# KeypadDisplayConnectors.net
KiCad netlist of a schematic drawn in Altium Designer
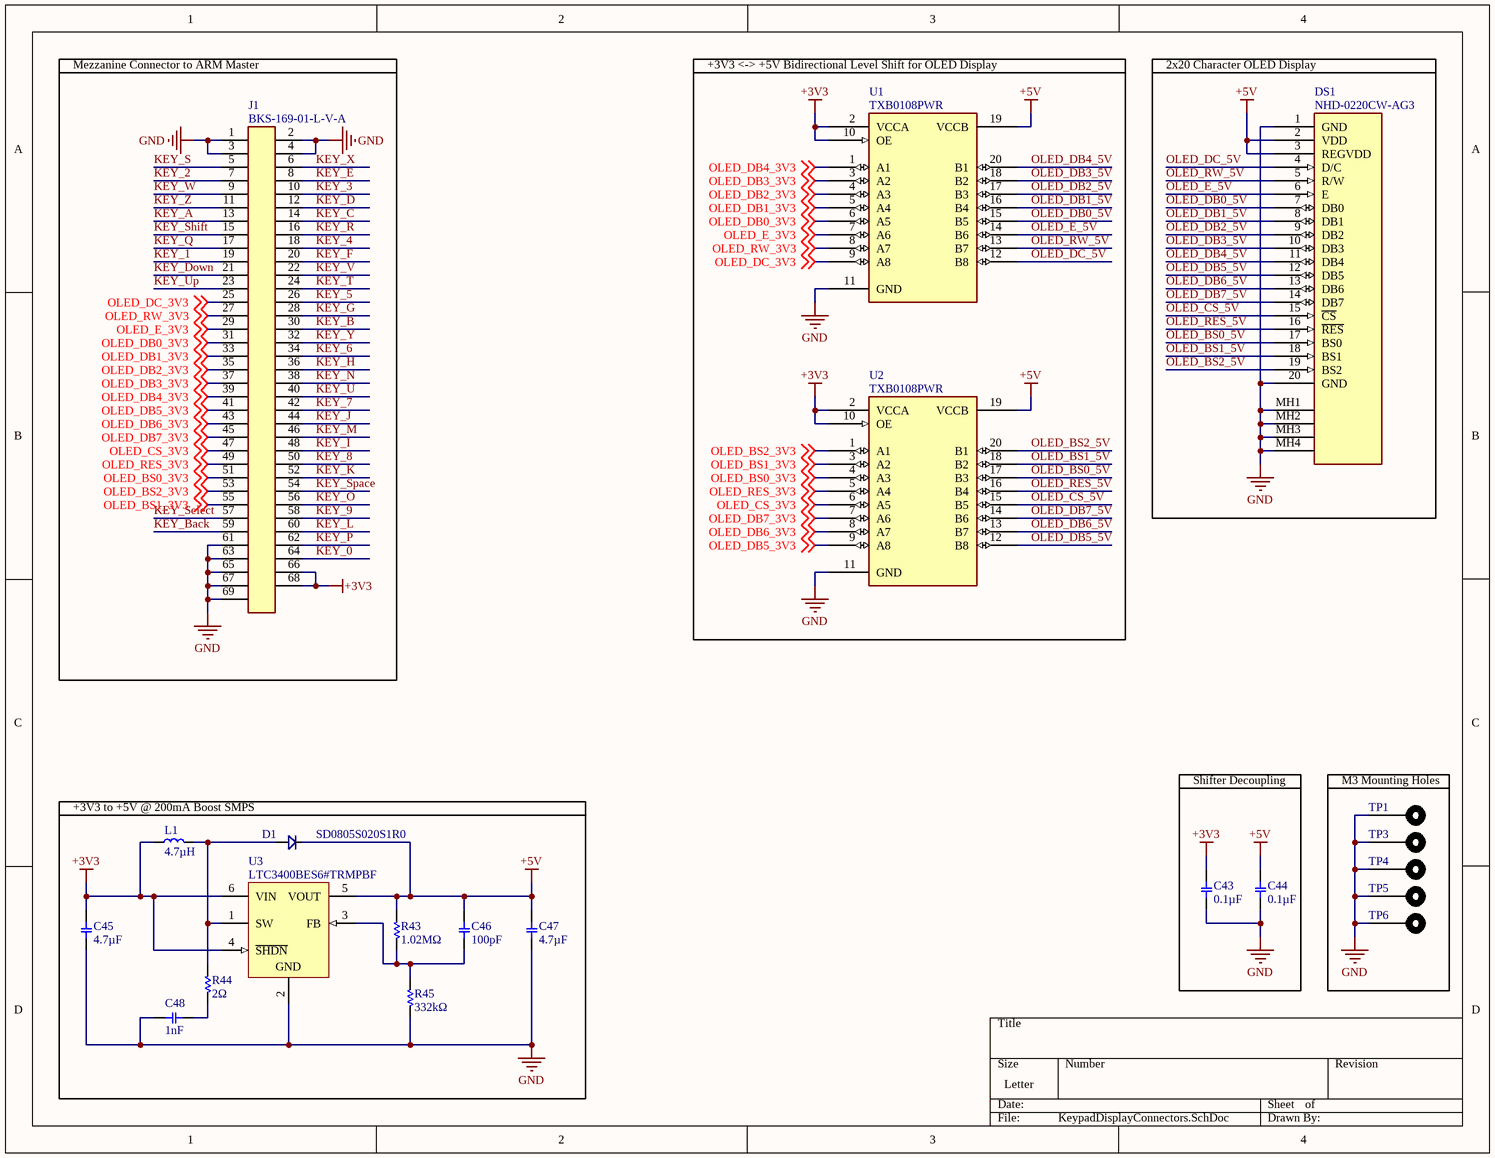
[diagram p0: KeypadDisplayConnectors.SchDoc]

(export (version "E")
  (design (tool "Eeschema 10.0.6"))
  (components
    (comp (ref "C43")
      (value "0.1µF")
      (footprint "C0805(2012)_NP_med")
      (description "SMT Capacitor")
      (fields (field (name "TOLERANCE") "X7R"))
      (libsource (lib "ChipComponents") (part "CPN_SMT"))
    )
    (comp (ref "C44")
      (value "0.1µF")
      (footprint "C0805(2012)_NP_med")
      (description "SMT Capacitor")
      (fields (field (name "TOLERANCE") "X7R"))
      (libsource (lib "ChipComponents") (part "CPN_SMT"))
    )
    (comp (ref "C45")
      (value "4.7µF")
      (footprint "C0805(2012)_NP_med")
      (description "SMT Capacitor")
      (fields (field (name "MANUFACTURER") "Taiyo Yuden") (field (name "PART NUMBER") "JMK212BJ475MG"))
      (libsource (lib "ChipComponents") (part "CPN_SMT"))
    )
    (comp (ref "C46")
      (value "100pF")
      (footprint "C0805(2012)_NP_med")
      (description "SMT Capacitor")
      (fields (field (name "TOLERANCE") "X7R"))
      (libsource (lib "ChipComponents") (part "CPN_SMT"))
    )
    (comp (ref "C47")
      (value "4.7µF")
      (footprint "C0805(2012)_NP_med")
      (description "SMT Capacitor")
      (fields (field (name "MANUFACTURER") "Taiyo Yuden") (field (name "PART NUMBER") "JMK212BJ475MG"))
      (libsource (lib "ChipComponents") (part "CPN_SMT"))
    )
    (comp (ref "C48")
      (value "1nF")
      (footprint "C0805(2012)_NP_med")
      (description "SMT Capacitor")
      (fields (field (name "TOLERANCE") "X7R"))
      (libsource (lib "ChipComponents") (part "CPN_SMT"))
    )
    (comp (ref "D1")
      (value "SD0805S020S1R0")
      (footprint "C0805(2012)_P_med")
      (description "SMT LED")
      (fields (field (name "MANUFACTURER") "AVX"))
      (libsource (lib "ChipComponents") (part "DIODE_sMT"))
    )
    (comp (ref "DS1")
      (value "NHD-0220CW-AG3")
      (footprint "Newhaven NHD-0220CW-AG3")
      (fields (field (name "MANUFACTURER") "Newhaven Display Intl"))
      (libsource (lib "RFIDSchematicLibrary") (part "NewHaven NHD-0220CW-AG3"))
    )
    (comp (ref "J1")
      (value "BKS-169-01-L-V-A")
      (footprint "SAMTEC BKS-169-01-L-V-A")
      (description "CONN HDR 69POS 1MM SMD GLD")
      (libsource (lib "RFIDSchematicLibrary") (part "Samtec BKS-169-01-L-V-A"))
    )
    (comp (ref "L1")
      (value "4.7µH")
      (footprint "C0805(2012)_NP_med")
      (description "SMT Inductor")
      (fields (field (name "MANUFACTURER") "Murata") (field (name "PART NUMBER") "LQM2MPN4R7MG0L"))
      (libsource (lib "ChipComponents") (part "IND_SMT"))
    )
    (comp (ref "R43")
      (value "1.02MΩ")
      (footprint "R0805(2012)_med")
      (description "SMT resistor")
      (fields (field (name "TOLERANCE") "1%"))
      (libsource (lib "ChipComponents") (part "RES_SMT"))
    )
    (comp (ref "R44")
      (value "2Ω")
      (footprint "R0805(2012)_med")
      (description "SMT resistor")
      (fields (field (name "TOLERANCE") "1%"))
      (libsource (lib "ChipComponents") (part "RES_SMT"))
    )
    (comp (ref "R45")
      (value "332kΩ")
      (footprint "R0805(2012)_med")
      (description "SMT resistor")
      (fields (field (name "TOLERANCE") "1%"))
      (libsource (lib "ChipComponents") (part "RES_SMT"))
    )
    (comp (ref "TP1")
      (value "Testpoint")
      (footprint "M3x0.5 Hole")
      (libsource (lib "RFIDSchematicLibrary") (part "Testpoint"))
    )
    (comp (ref "TP3")
      (value "Testpoint")
      (footprint "M3x0.5 Hole")
      (libsource (lib "RFIDSchematicLibrary") (part "Testpoint"))
    )
    (comp (ref "TP4")
      (value "Testpoint")
      (footprint "M3x0.5 Hole")
      (libsource (lib "RFIDSchematicLibrary") (part "Testpoint"))
    )
    (comp (ref "TP5")
      (value "Testpoint")
      (footprint "M3x0.5 Hole")
      (libsource (lib "RFIDSchematicLibrary") (part "Testpoint"))
    )
    (comp (ref "TP6")
      (value "Testpoint")
      (footprint "M3x0.5 Hole")
      (libsource (lib "RFIDSchematicLibrary") (part "Testpoint"))
    )
    (comp (ref "U1")
      (value "TXB0108PWR")
      (footprint "TI 20 Pin PW (R-PDSO-G20)")
      (description "IC 8-BIT TRNSTR 15KV ESD 20TSSOP")
      (fields (field (name "MANUFACTURER") "Texas Instruments"))
      (libsource (lib "RFIDSchematicLibrary") (part "TI TXB0108PWR"))
    )
    (comp (ref "U2")
      (value "TXB0108PWR")
      (footprint "TI 20 Pin PW (R-PDSO-G20)")
      (description "IC 8-BIT TRNSTR 15KV ESD 20TSSOP")
      (fields (field (name "MANUFACTURER") "Texas Instruments"))
      (libsource (lib "RFIDSchematicLibrary") (part "TI TXB0108PWR"))
    )
    (comp (ref "U3")
      (value "LTC3400BES6#TRMPBF")
      (footprint "LT-S6-6-TSOT-23_N")
      (fields (field (name "MANUFACTURER") "Linear Technology"))
      (libsource (lib "Linear Technology Power Management Switching Regulator LTC1174-LTC3901") (part "LTC3400BES6#TRMPBF"))
    )
  )
  (nets
    (net (code "1") (name "+3V3") (class "Default")
      (node (ref "C43") (pin "1") (pinfunction "1_1") (pintype "passive"))
      (node (ref "C45") (pin "1") (pinfunction "1_1") (pintype "passive"))
      (node (ref "J1") (pin "66") (pinfunction "66_66") (pintype "passive"))
      (node (ref "J1") (pin "68") (pinfunction "68_68") (pintype "passive"))
      (node (ref "L1") (pin "1") (pinfunction "1_1") (pintype "passive"))
      (node (ref "U1") (pin "10") (pinfunction "OE_10") (pintype "input"))
      (node (ref "U1") (pin "2") (pinfunction "VCCA_2") (pintype "power_in"))
      (node (ref "U2") (pin "10") (pinfunction "OE_10") (pintype "input"))
      (node (ref "U2") (pin "2") (pinfunction "VCCA_2") (pintype "power_in"))
      (node (ref "U3") (pin "4") (pinfunction "~{SHDN}_4") (pintype "input"))
      (node (ref "U3") (pin "6") (pinfunction "VIN_6") (pintype "power_in"))
    )
    (net (code "2") (name "+5V") (class "Default")
      (node (ref "C44") (pin "1") (pinfunction "1_1") (pintype "passive"))
      (node (ref "C46") (pin "1") (pinfunction "1_1") (pintype "passive"))
      (node (ref "C47") (pin "1") (pinfunction "1_1") (pintype "passive"))
      (node (ref "D1") (pin "1") (pinfunction "K_1") (pintype "passive"))
      (node (ref "DS1") (pin "2") (pinfunction "VDD_2") (pintype "power_in"))
      (node (ref "DS1") (pin "3") (pinfunction "REGVDD_3") (pintype "power_in"))
      (node (ref "R43") (pin "1") (pinfunction "1_1") (pintype "passive"))
      (node (ref "U1") (pin "19") (pinfunction "VCCB_19") (pintype "power_in"))
      (node (ref "U2") (pin "19") (pinfunction "VCCB_19") (pintype "power_in"))
      (node (ref "U3") (pin "5") (pinfunction "VOUT_5") (pintype "power_in"))
    )
    (net (code "3") (name "/KEY_0") (class "Default")
      (node (ref "J1") (pin "64") (pinfunction "64_64") (pintype "passive"))
    )
    (net (code "4") (name "/KEY_1") (class "Default")
      (node (ref "J1") (pin "19") (pinfunction "19_19") (pintype "passive"))
    )
    (net (code "5") (name "/KEY_2") (class "Default")
      (node (ref "J1") (pin "7") (pinfunction "7_7") (pintype "passive"))
    )
    (net (code "6") (name "/KEY_3") (class "Default")
      (node (ref "J1") (pin "10") (pinfunction "10_10") (pintype "passive"))
    )
    (net (code "7") (name "/KEY_4") (class "Default")
      (node (ref "J1") (pin "18") (pinfunction "18_18") (pintype "passive"))
    )
    (net (code "8") (name "/KEY_5") (class "Default")
      (node (ref "J1") (pin "26") (pinfunction "26_26") (pintype "passive"))
    )
    (net (code "9") (name "/KEY_6") (class "Default")
      (node (ref "J1") (pin "34") (pinfunction "34_34") (pintype "passive"))
    )
    (net (code "10") (name "/KEY_7") (class "Default")
      (node (ref "J1") (pin "42") (pinfunction "42_42") (pintype "passive"))
    )
    (net (code "11") (name "/KEY_8") (class "Default")
      (node (ref "J1") (pin "50") (pinfunction "50_50") (pintype "passive"))
    )
    (net (code "12") (name "/KEY_9") (class "Default")
      (node (ref "J1") (pin "58") (pinfunction "58_58") (pintype "passive"))
    )
    (net (code "13") (name "/KEY_A") (class "Default")
      (node (ref "J1") (pin "13") (pinfunction "13_13") (pintype "passive"))
    )
    (net (code "14") (name "/KEY_B") (class "Default")
      (node (ref "J1") (pin "30") (pinfunction "30_30") (pintype "passive"))
    )
    (net (code "15") (name "/KEY_Back") (class "Default")
      (node (ref "J1") (pin "59") (pinfunction "59_59") (pintype "passive"))
    )
    (net (code "16") (name "/KEY_C") (class "Default")
      (node (ref "J1") (pin "14") (pinfunction "14_14") (pintype "passive"))
    )
    (net (code "17") (name "/KEY_D") (class "Default")
      (node (ref "J1") (pin "12") (pinfunction "12_12") (pintype "passive"))
    )
    (net (code "18") (name "/KEY_Down") (class "Default")
      (node (ref "J1") (pin "21") (pinfunction "21_21") (pintype "passive"))
    )
    (net (code "19") (name "/KEY_E") (class "Default")
      (node (ref "J1") (pin "8") (pinfunction "8_8") (pintype "passive"))
    )
    (net (code "20") (name "/KEY_F") (class "Default")
      (node (ref "J1") (pin "20") (pinfunction "20_20") (pintype "passive"))
    )
    (net (code "21") (name "/KEY_G") (class "Default")
      (node (ref "J1") (pin "28") (pinfunction "28_28") (pintype "passive"))
    )
    (net (code "22") (name "/KEY_H") (class "Default")
      (node (ref "J1") (pin "36") (pinfunction "36_36") (pintype "passive"))
    )
    (net (code "23") (name "/KEY_I") (class "Default")
      (node (ref "J1") (pin "48") (pinfunction "48_48") (pintype "passive"))
    )
    (net (code "24") (name "/KEY_J") (class "Default")
      (node (ref "J1") (pin "44") (pinfunction "44_44") (pintype "passive"))
    )
    (net (code "25") (name "/KEY_K") (class "Default")
      (node (ref "J1") (pin "52") (pinfunction "52_52") (pintype "passive"))
    )
    (net (code "26") (name "/KEY_L") (class "Default")
      (node (ref "J1") (pin "60") (pinfunction "60_60") (pintype "passive"))
    )
    (net (code "27") (name "/KEY_M") (class "Default")
      (node (ref "J1") (pin "46") (pinfunction "46_46") (pintype "passive"))
    )
    (net (code "28") (name "/KEY_N") (class "Default")
      (node (ref "J1") (pin "38") (pinfunction "38_38") (pintype "passive"))
    )
    (net (code "29") (name "/KEY_O") (class "Default")
      (node (ref "J1") (pin "56") (pinfunction "56_56") (pintype "passive"))
    )
    (net (code "30") (name "/KEY_P") (class "Default")
      (node (ref "J1") (pin "62") (pinfunction "62_62") (pintype "passive"))
    )
    (net (code "31") (name "/KEY_Q") (class "Default")
      (node (ref "J1") (pin "17") (pinfunction "17_17") (pintype "passive"))
    )
    (net (code "32") (name "/KEY_R") (class "Default")
      (node (ref "J1") (pin "16") (pinfunction "16_16") (pintype "passive"))
    )
    (net (code "33") (name "/KEY_S") (class "Default")
      (node (ref "J1") (pin "5") (pinfunction "5_5") (pintype "passive"))
    )
    (net (code "34") (name "/KEY_Select") (class "Default")
      (node (ref "J1") (pin "57") (pinfunction "57_57") (pintype "passive"))
    )
    (net (code "35") (name "/KEY_Shift") (class "Default")
      (node (ref "J1") (pin "15") (pinfunction "15_15") (pintype "passive"))
    )
    (net (code "36") (name "/KEY_Space") (class "Default")
      (node (ref "J1") (pin "54") (pinfunction "54_54") (pintype "passive"))
    )
    (net (code "37") (name "/KEY_T") (class "Default")
      (node (ref "J1") (pin "24") (pinfunction "24_24") (pintype "passive"))
    )
    (net (code "38") (name "/KEY_U") (class "Default")
      (node (ref "J1") (pin "40") (pinfunction "40_40") (pintype "passive"))
    )
    (net (code "39") (name "/KEY_Up") (class "Default")
      (node (ref "J1") (pin "23") (pinfunction "23_23") (pintype "passive"))
    )
    (net (code "40") (name "/KEY_V") (class "Default")
      (node (ref "J1") (pin "22") (pinfunction "22_22") (pintype "passive"))
    )
    (net (code "41") (name "/KEY_W") (class "Default")
      (node (ref "J1") (pin "9") (pinfunction "9_9") (pintype "passive"))
    )
    (net (code "42") (name "/KEY_X") (class "Default")
      (node (ref "J1") (pin "6") (pinfunction "6_6") (pintype "passive"))
    )
    (net (code "43") (name "/KEY_Y") (class "Default")
      (node (ref "J1") (pin "32") (pinfunction "32_32") (pintype "passive"))
    )
    (net (code "44") (name "/KEY_Z") (class "Default")
      (node (ref "J1") (pin "11") (pinfunction "11_11") (pintype "passive"))
    )
    (net (code "45") (name "/OLED_BS0_5V") (class "Default")
      (node (ref "DS1") (pin "17") (pinfunction "BS0_17") (pintype "input"))
      (node (ref "U2") (pin "17") (pinfunction "B3_17") (pintype "bidirectional"))
    )
    (net (code "46") (name "/OLED_BS1_5V") (class "Default")
      (node (ref "DS1") (pin "18") (pinfunction "BS1_18") (pintype "input"))
      (node (ref "U2") (pin "18") (pinfunction "B2_18") (pintype "bidirectional"))
    )
    (net (code "47") (name "/OLED_BS2_5V") (class "Default")
      (node (ref "DS1") (pin "19") (pinfunction "BS2_19") (pintype "input"))
      (node (ref "U2") (pin "20") (pinfunction "B1_20") (pintype "bidirectional"))
    )
    (net (code "48") (name "/OLED_CS_5V") (class "Default")
      (node (ref "DS1") (pin "15") (pinfunction "~{CS}_15") (pintype "input"))
      (node (ref "U2") (pin "15") (pinfunction "B5_15") (pintype "bidirectional"))
    )
    (net (code "49") (name "/OLED_DB0_5V") (class "Default")
      (node (ref "DS1") (pin "7") (pinfunction "DB0_7") (pintype "bidirectional"))
      (node (ref "U1") (pin "15") (pinfunction "B5_15") (pintype "bidirectional"))
    )
    (net (code "50") (name "/OLED_DB1_5V") (class "Default")
      (node (ref "DS1") (pin "8") (pinfunction "DB1_8") (pintype "bidirectional"))
      (node (ref "U1") (pin "16") (pinfunction "B4_16") (pintype "bidirectional"))
    )
    (net (code "51") (name "/OLED_DB2_5V") (class "Default")
      (node (ref "DS1") (pin "9") (pinfunction "DB2_9") (pintype "bidirectional"))
      (node (ref "U1") (pin "17") (pinfunction "B3_17") (pintype "bidirectional"))
    )
    (net (code "52") (name "/OLED_DB3_5V") (class "Default")
      (node (ref "DS1") (pin "10") (pinfunction "DB3_10") (pintype "bidirectional"))
      (node (ref "U1") (pin "18") (pinfunction "B2_18") (pintype "bidirectional"))
    )
    (net (code "53") (name "/OLED_DB4_5V") (class "Default")
      (node (ref "DS1") (pin "11") (pinfunction "DB4_11") (pintype "bidirectional"))
      (node (ref "U1") (pin "20") (pinfunction "B1_20") (pintype "bidirectional"))
    )
    (net (code "54") (name "/OLED_DB5_5V") (class "Default")
      (node (ref "DS1") (pin "12") (pinfunction "DB5_12") (pintype "bidirectional"))
      (node (ref "U2") (pin "12") (pinfunction "B8_12") (pintype "bidirectional"))
    )
    (net (code "55") (name "/OLED_DB6_5V") (class "Default")
      (node (ref "DS1") (pin "13") (pinfunction "DB6_13") (pintype "bidirectional"))
      (node (ref "U2") (pin "13") (pinfunction "B7_13") (pintype "bidirectional"))
    )
    (net (code "56") (name "/OLED_DB7_5V") (class "Default")
      (node (ref "DS1") (pin "14") (pinfunction "DB7_14") (pintype "bidirectional"))
      (node (ref "U2") (pin "14") (pinfunction "B6_14") (pintype "bidirectional"))
    )
    (net (code "57") (name "/OLED_DC_5V") (class "Default")
      (node (ref "DS1") (pin "4") (pinfunction "D/C_4") (pintype "input"))
      (node (ref "U1") (pin "12") (pinfunction "B8_12") (pintype "bidirectional"))
    )
    (net (code "58") (name "/OLED_E_5V") (class "Default")
      (node (ref "DS1") (pin "6") (pinfunction "E_6") (pintype "input"))
      (node (ref "U1") (pin "14") (pinfunction "B6_14") (pintype "bidirectional"))
    )
    (net (code "59") (name "/OLED_RES_5V") (class "Default")
      (node (ref "DS1") (pin "16") (pinfunction "~{RES}_16") (pintype "input"))
      (node (ref "U2") (pin "16") (pinfunction "B4_16") (pintype "bidirectional"))
    )
    (net (code "60") (name "/OLED_RW_5V") (class "Default")
      (node (ref "DS1") (pin "5") (pinfunction "R/W_5") (pintype "input"))
      (node (ref "U1") (pin "13") (pinfunction "B7_13") (pintype "bidirectional"))
    )
    (net (code "61") (name "GND") (class "Default")
      (node (ref "C43") (pin "2") (pinfunction "2_2") (pintype "passive"))
      (node (ref "C44") (pin "2") (pinfunction "2_2") (pintype "passive"))
      (node (ref "C45") (pin "2") (pinfunction "2_2") (pintype "passive"))
      (node (ref "C47") (pin "2") (pinfunction "2_2") (pintype "passive"))
      (node (ref "C48") (pin "1") (pinfunction "1_1") (pintype "passive"))
      (node (ref "DS1") (pin "1") (pinfunction "GND_1") (pintype "power_in"))
      (node (ref "DS1") (pin "20") (pinfunction "GND_20") (pintype "power_in"))
      (node (ref "DS1") (pin "MH1") (pinfunction "MH1_MH1") (pintype "passive"))
      (node (ref "DS1") (pin "MH2") (pinfunction "MH2_MH2") (pintype "passive"))
      (node (ref "DS1") (pin "MH3") (pinfunction "MH3_MH3") (pintype "passive"))
      (node (ref "DS1") (pin "MH4") (pinfunction "MH4_MH4") (pintype "passive"))
      (node (ref "J1") (pin "1") (pinfunction "1_1") (pintype "passive"))
      (node (ref "J1") (pin "2") (pinfunction "2_2") (pintype "passive"))
      (node (ref "J1") (pin "3") (pinfunction "3_3") (pintype "passive"))
      (node (ref "J1") (pin "4") (pinfunction "4_4") (pintype "passive"))
      (node (ref "J1") (pin "61") (pinfunction "61_61") (pintype "passive"))
      (node (ref "J1") (pin "63") (pinfunction "63_63") (pintype "passive"))
      (node (ref "J1") (pin "65") (pinfunction "65_65") (pintype "passive"))
      (node (ref "J1") (pin "67") (pinfunction "67_67") (pintype "passive"))
      (node (ref "J1") (pin "69") (pinfunction "69_69") (pintype "passive"))
      (node (ref "R45") (pin "2") (pinfunction "2_2") (pintype "passive"))
      (node (ref "TP1") (pin "1") (pinfunction "1_1") (pintype "passive"))
      (node (ref "TP3") (pin "1") (pinfunction "1_1") (pintype "passive"))
      (node (ref "TP4") (pin "1") (pinfunction "1_1") (pintype "passive"))
      (node (ref "TP5") (pin "1") (pinfunction "1_1") (pintype "passive"))
      (node (ref "TP6") (pin "1") (pinfunction "1_1") (pintype "passive"))
      (node (ref "U1") (pin "11") (pinfunction "GND_11") (pintype "power_in"))
      (node (ref "U2") (pin "11") (pinfunction "GND_11") (pintype "power_in"))
      (node (ref "U3") (pin "2") (pinfunction "GND_2") (pintype "power_in"))
    )
    (net (code "62") (name "Net-(C48-Pad2)") (class "Default")
      (node (ref "C48") (pin "2") (pinfunction "2_2") (pintype "passive"))
      (node (ref "R44") (pin "2") (pinfunction "2_2") (pintype "passive"))
    )
    (net (code "63") (name "Net-(D1-A)") (class "Default")
      (node (ref "D1") (pin "2") (pinfunction "A_2") (pintype "passive"))
      (node (ref "L1") (pin "2") (pinfunction "2_2") (pintype "passive"))
      (node (ref "R44") (pin "1") (pinfunction "1_1") (pintype "passive"))
      (node (ref "U3") (pin "1") (pinfunction "SW_1") (pintype "passive"))
    )
    (net (code "64") (name "Net-(U3-FB)") (class "Default")
      (node (ref "C46") (pin "2") (pinfunction "2_2") (pintype "passive"))
      (node (ref "R43") (pin "2") (pinfunction "2_2") (pintype "passive"))
      (node (ref "R45") (pin "1") (pinfunction "1_1") (pintype "passive"))
      (node (ref "U3") (pin "3") (pinfunction "FB_3") (pintype "input"))
    )
    (net (code "65") (name "OLED_BS0_3V3") (class "Default")
      (node (ref "J1") (pin "51") (pinfunction "51_51") (pintype "passive"))
      (node (ref "U2") (pin "4") (pinfunction "A3_4") (pintype "bidirectional"))
    )
    (net (code "66") (name "OLED_BS1_3V3") (class "Default")
      (node (ref "J1") (pin "55") (pinfunction "55_55") (pintype "passive"))
      (node (ref "U2") (pin "3") (pinfunction "A2_3") (pintype "bidirectional"))
    )
    (net (code "67") (name "OLED_BS2_3V3") (class "Default")
      (node (ref "J1") (pin "53") (pinfunction "53_53") (pintype "passive"))
      (node (ref "U2") (pin "1") (pinfunction "A1_1") (pintype "bidirectional"))
    )
    (net (code "68") (name "OLED_CS_3V3") (class "Default")
      (node (ref "J1") (pin "47") (pinfunction "47_47") (pintype "passive"))
      (node (ref "U2") (pin "6") (pinfunction "A5_6") (pintype "bidirectional"))
    )
    (net (code "69") (name "OLED_DB0_3V3") (class "Default")
      (node (ref "J1") (pin "31") (pinfunction "31_31") (pintype "passive"))
      (node (ref "U1") (pin "6") (pinfunction "A5_6") (pintype "bidirectional"))
    )
    (net (code "70") (name "OLED_DB1_3V3") (class "Default")
      (node (ref "J1") (pin "33") (pinfunction "33_33") (pintype "passive"))
      (node (ref "U1") (pin "5") (pinfunction "A4_5") (pintype "bidirectional"))
    )
    (net (code "71") (name "OLED_DB2_3V3") (class "Default")
      (node (ref "J1") (pin "35") (pinfunction "35_35") (pintype "passive"))
      (node (ref "U1") (pin "4") (pinfunction "A3_4") (pintype "bidirectional"))
    )
    (net (code "72") (name "OLED_DB3_3V3") (class "Default")
      (node (ref "J1") (pin "37") (pinfunction "37_37") (pintype "passive"))
      (node (ref "U1") (pin "3") (pinfunction "A2_3") (pintype "bidirectional"))
    )
    (net (code "73") (name "OLED_DB4_3V3") (class "Default")
      (node (ref "J1") (pin "39") (pinfunction "39_39") (pintype "passive"))
      (node (ref "U1") (pin "1") (pinfunction "A1_1") (pintype "bidirectional"))
    )
    (net (code "74") (name "OLED_DB5_3V3") (class "Default")
      (node (ref "J1") (pin "41") (pinfunction "41_41") (pintype "passive"))
      (node (ref "U2") (pin "9") (pinfunction "A8_9") (pintype "bidirectional"))
    )
    (net (code "75") (name "OLED_DB6_3V3") (class "Default")
      (node (ref "J1") (pin "43") (pinfunction "43_43") (pintype "passive"))
      (node (ref "U2") (pin "8") (pinfunction "A7_8") (pintype "bidirectional"))
    )
    (net (code "76") (name "OLED_DB7_3V3") (class "Default")
      (node (ref "J1") (pin "45") (pinfunction "45_45") (pintype "passive"))
      (node (ref "U2") (pin "7") (pinfunction "A6_7") (pintype "bidirectional"))
    )
    (net (code "77") (name "OLED_DC_3V3") (class "Default")
      (node (ref "J1") (pin "25") (pinfunction "25_25") (pintype "passive"))
      (node (ref "U1") (pin "9") (pinfunction "A8_9") (pintype "bidirectional"))
    )
    (net (code "78") (name "OLED_E_3V3") (class "Default")
      (node (ref "J1") (pin "29") (pinfunction "29_29") (pintype "passive"))
      (node (ref "U1") (pin "7") (pinfunction "A6_7") (pintype "bidirectional"))
    )
    (net (code "79") (name "OLED_RES_3V3") (class "Default")
      (node (ref "J1") (pin "49") (pinfunction "49_49") (pintype "passive"))
      (node (ref "U2") (pin "5") (pinfunction "A4_5") (pintype "bidirectional"))
    )
    (net (code "80") (name "OLED_RW_3V3") (class "Default")
      (node (ref "J1") (pin "27") (pinfunction "27_27") (pintype "passive"))
      (node (ref "U1") (pin "8") (pinfunction "A7_8") (pintype "bidirectional"))
    )
  )
)
